# UnknownWatch_Top.net
KiCad netlist of a schematic drawn in EAGLE
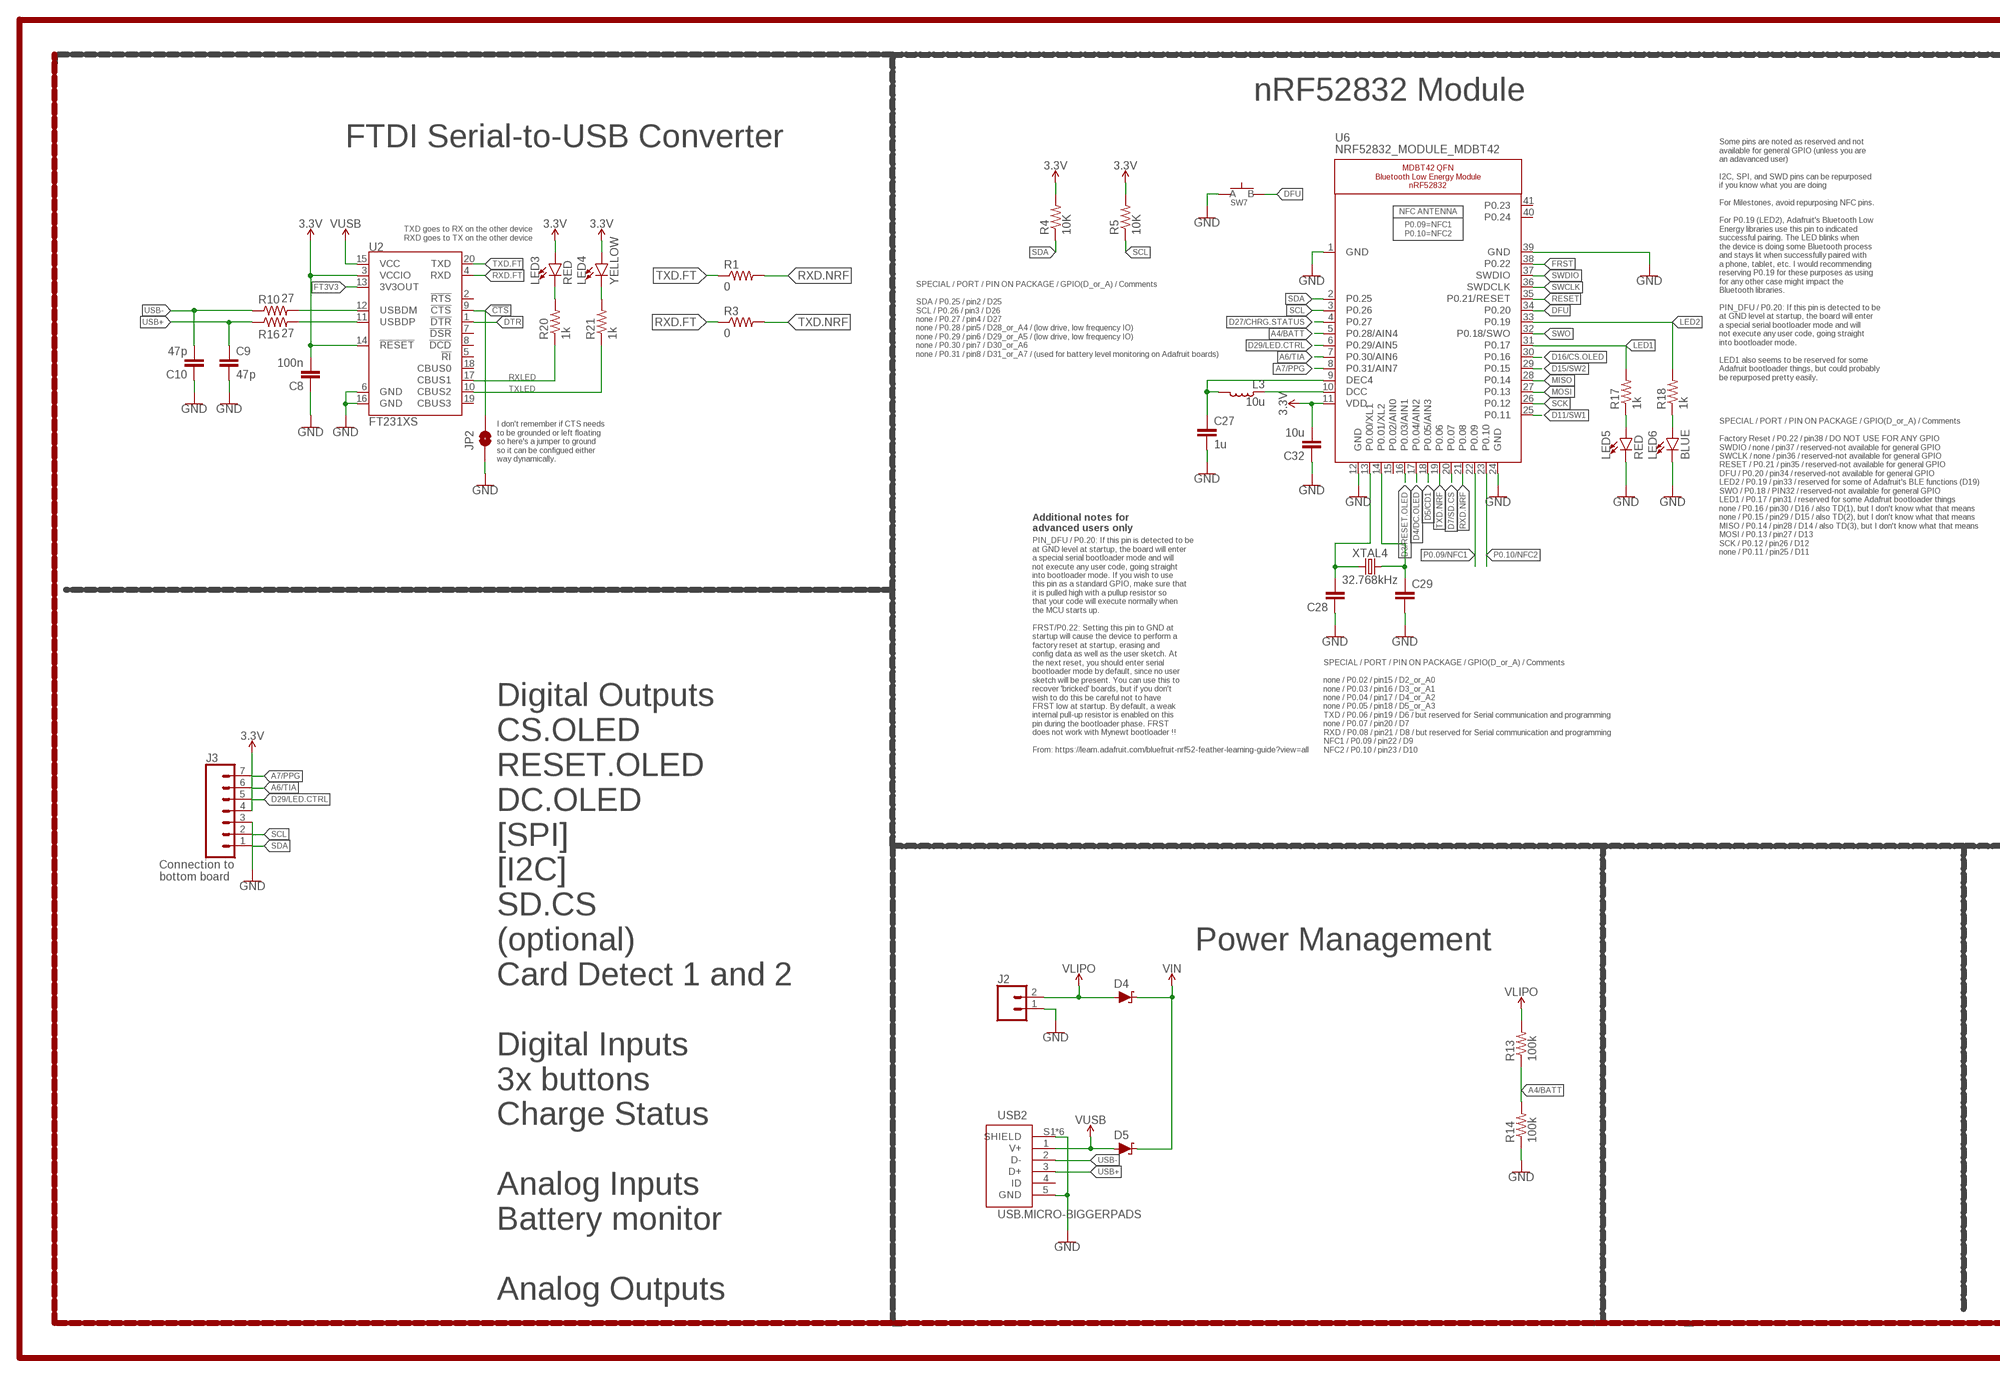
[diagram p0: schematic, sheet 1, part 1 of 2]
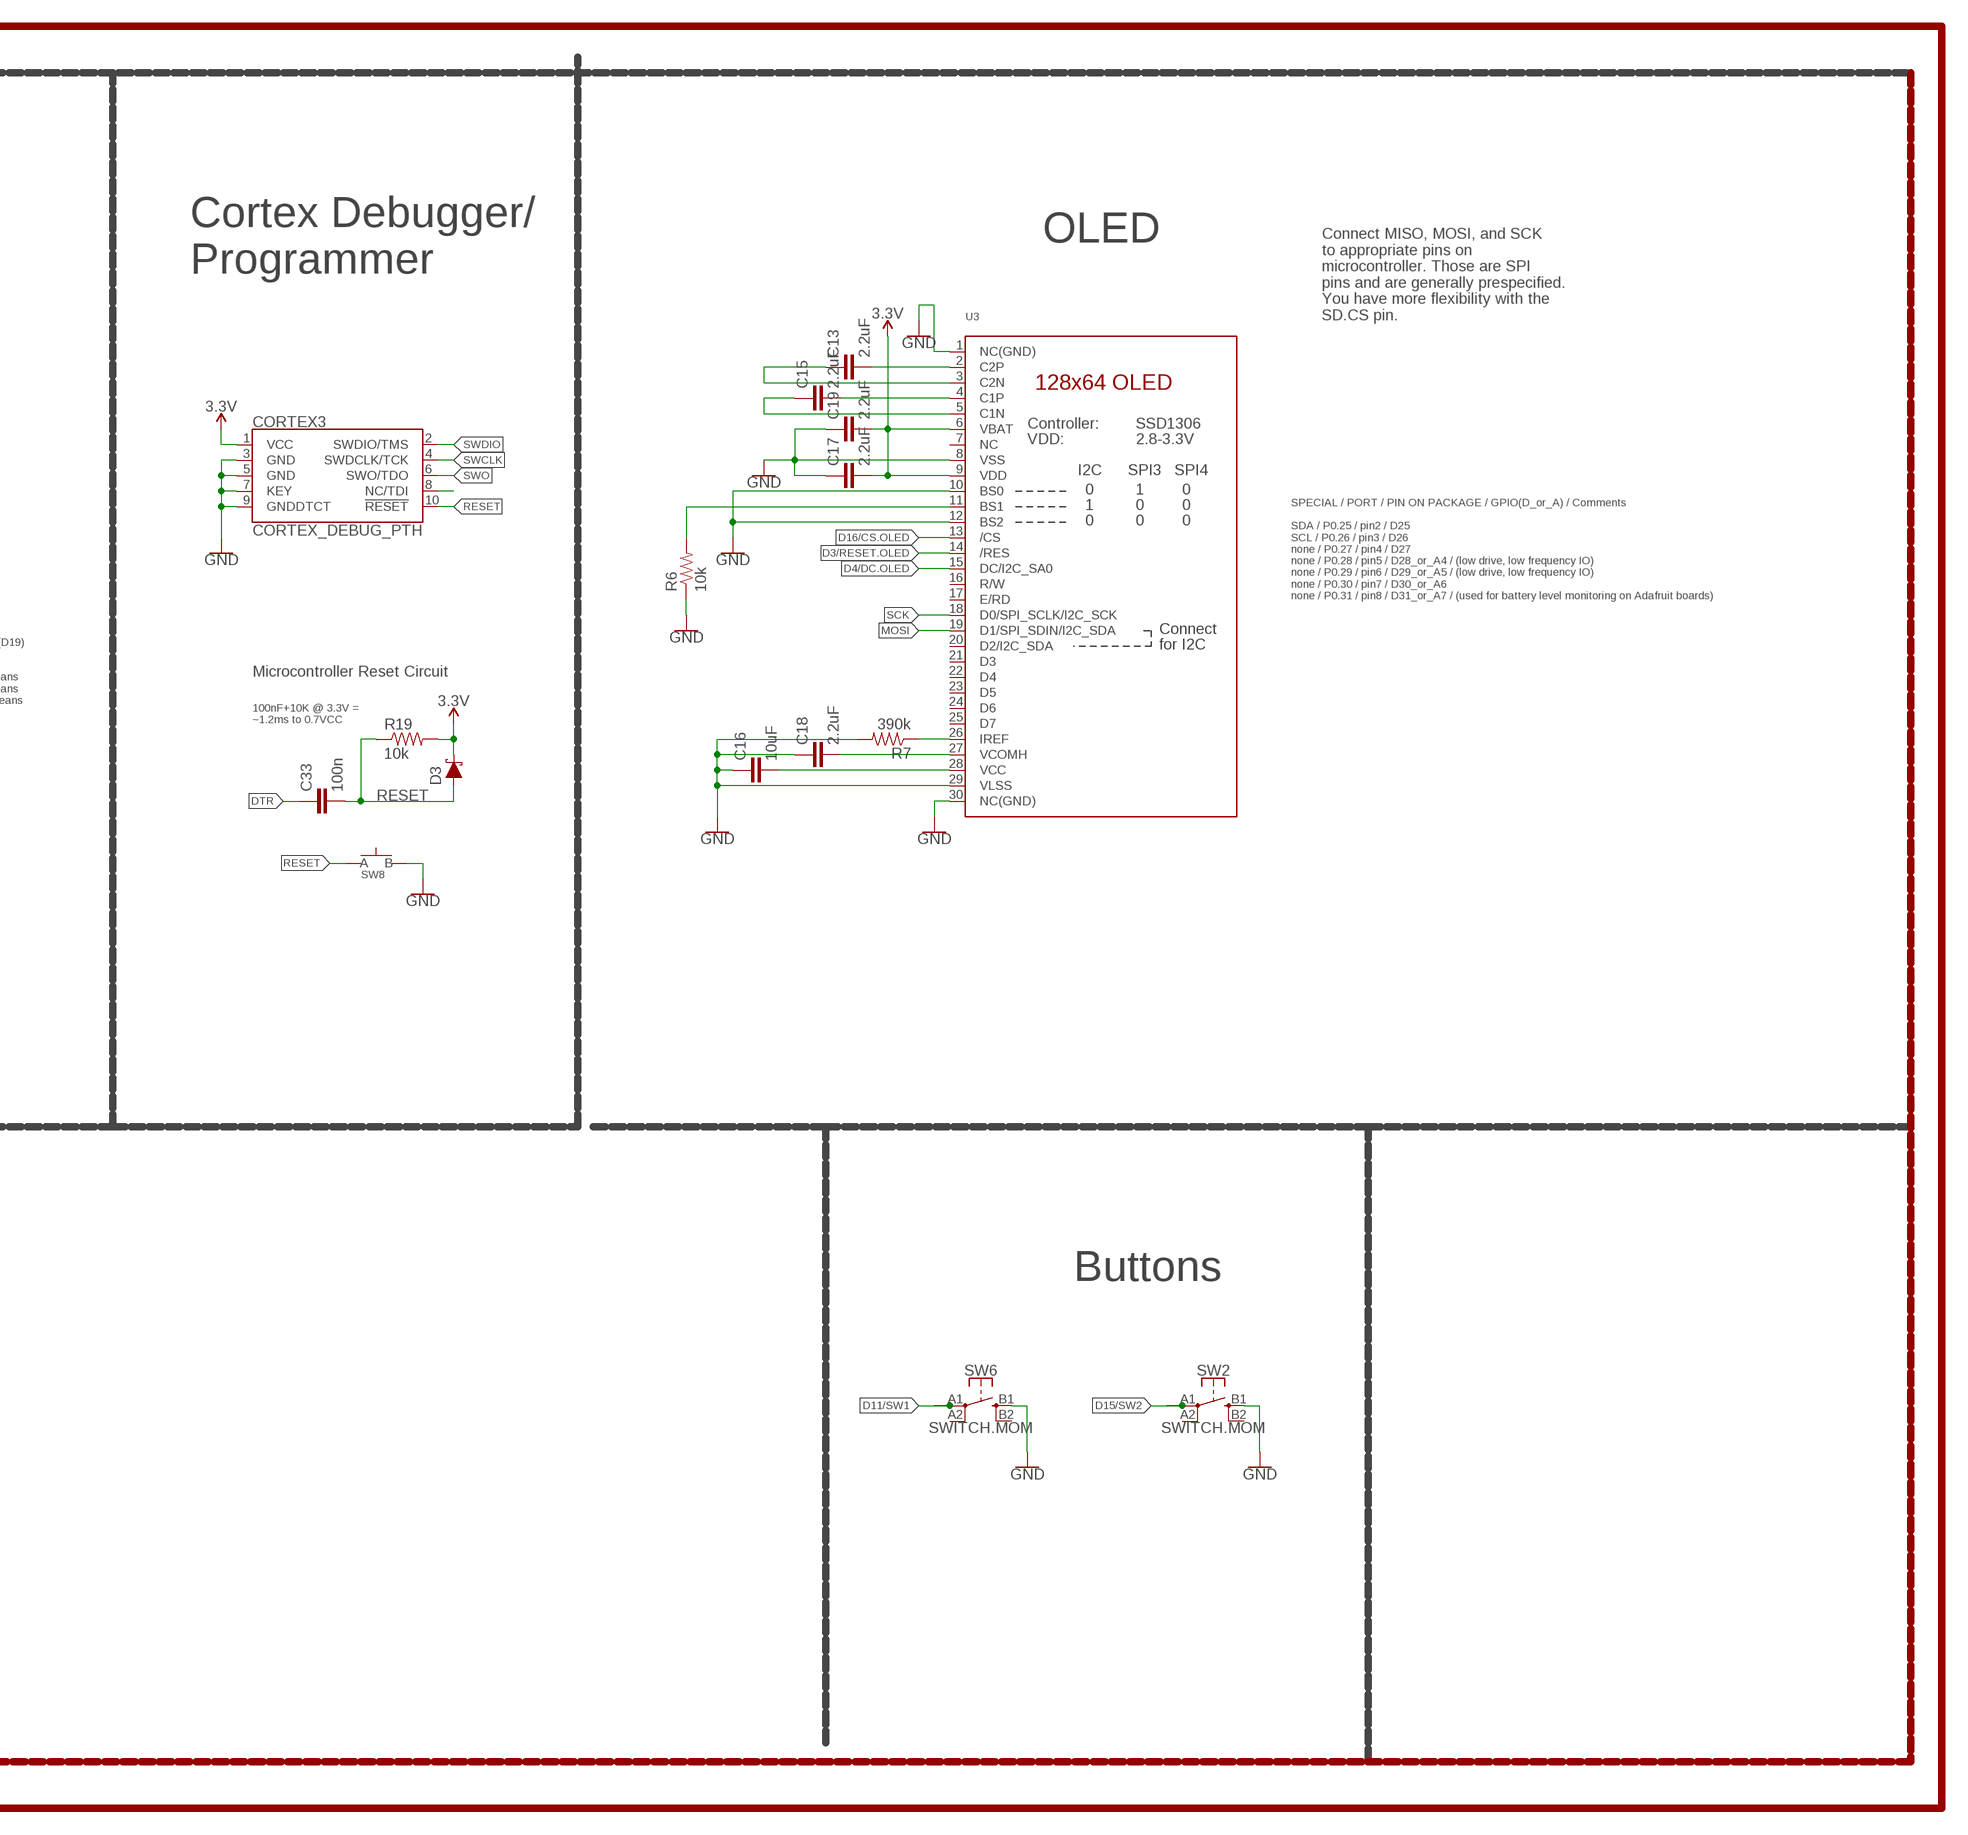
[diagram p1: schematic, sheet 1, part 2 of 2]

(export (version "E")
  (design (tool "Eeschema 10.0.6"))
  (components
    (comp (ref "C8")
      (value "100n")
      (footprint "eagle-import:C0603")
      (libsource (lib "eagle-import") (part "CAPACITOR0603"))
    )
    (comp (ref "C9")
      (value "47p")
      (footprint "eagle-import:C0603")
      (libsource (lib "eagle-import") (part "CAPACITOR0603"))
    )
    (comp (ref "C10")
      (value "47p")
      (footprint "eagle-import:C0603")
      (libsource (lib "eagle-import") (part "CAPACITOR0603"))
    )
    (comp (ref "C13")
      (value "2.2uF")
      (footprint "eagle-import:C0402")
      (libsource (lib "eagle-import") (part "CAPACITOR0402"))
    )
    (comp (ref "C15")
      (value "2.2uF")
      (footprint "eagle-import:C0402")
      (libsource (lib "eagle-import") (part "CAPACITOR0402"))
    )
    (comp (ref "C16")
      (value "10uF")
      (footprint "eagle-import:C0603")
      (libsource (lib "eagle-import") (part "CAPACITOR0603"))
    )
    (comp (ref "C17")
      (value "2.2uF")
      (footprint "eagle-import:C0402")
      (libsource (lib "eagle-import") (part "CAPACITOR0402"))
    )
    (comp (ref "C18")
      (value "2.2uF")
      (footprint "eagle-import:C0402")
      (libsource (lib "eagle-import") (part "CAPACITOR0402"))
    )
    (comp (ref "C19")
      (value "2.2uF")
      (footprint "eagle-import:C0402")
      (libsource (lib "eagle-import") (part "CAPACITOR0402"))
    )
    (comp (ref "C27")
      (value "1u")
      (footprint "eagle-import:C0603")
      (libsource (lib "eagle-import") (part "CAPACITOR0603"))
    )
    (comp (ref "C28")
      (value "CAPACITOR0603")
      (footprint "eagle-import:C0603")
      (libsource (lib "eagle-import") (part "CAPACITOR0603"))
    )
    (comp (ref "C29")
      (value "CAPACITOR0603")
      (footprint "eagle-import:C0603")
      (libsource (lib "eagle-import") (part "CAPACITOR0603"))
    )
    (comp (ref "C32")
      (value "10u")
      (footprint "eagle-import:C0805")
      (libsource (lib "eagle-import") (part "CAPACITOR0805"))
    )
    (comp (ref "C33")
      (value "100n")
      (footprint "eagle-import:C0603")
      (libsource (lib "eagle-import") (part "CAPACITOR0603"))
    )
    (comp (ref "CORTEX3")
      (value "CORTEX_DEBUG_PTH")
      (footprint "eagle-import:2X5-PTH-1.27MM")
      (libsource (lib "eagle-import") (part "CORTEX_DEBUG_PTH"))
    )
    (comp (ref "D3")
      (value "SCHOTTKY-USC")
      (footprint "eagle-import:USC")
      (libsource (lib "eagle-import") (part "SCHOTTKY-USC"))
    )
    (comp (ref "D4")
      (value "SCHOTTKY-USC")
      (footprint "eagle-import:USC")
      (libsource (lib "eagle-import") (part "SCHOTTKY-USC"))
    )
    (comp (ref "D5")
      (value "SCHOTTKY-USC")
      (footprint "eagle-import:USC")
      (libsource (lib "eagle-import") (part "SCHOTTKY-USC"))
    )
    (comp (ref "J2")
      (value "CONN_02")
      (footprint "eagle-import:1X02")
      (libsource (lib "eagle-import") (part "CONN_02"))
    )
    (comp (ref "J3")
      (value "CONN_07-1.27MM")
      (footprint "eagle-import:1X07_1.27MM")
      (libsource (lib "eagle-import") (part "CONN_07-1.27MM"))
    )
    (comp (ref "JP2")
      (value "JUMPER-SMT_2_NO_SILK")
      (footprint "eagle-import:SMT-JUMPER_2_NO_SILK")
      (libsource (lib "eagle-import") (part "JUMPER-SMT_2_NO_SILK"))
    )
    (comp (ref "L3")
      (value "10u")
      (footprint "eagle-import:L0603")
      (libsource (lib "eagle-import") (part "INDUCTOR0603"))
    )
    (comp (ref "LED3")
      (value "RED")
      (footprint "eagle-import:LED-0603")
      (libsource (lib "eagle-import") (part "LED0603"))
    )
    (comp (ref "LED4")
      (value "YELLOW")
      (footprint "eagle-import:LED-0603")
      (libsource (lib "eagle-import") (part "LED0603"))
    )
    (comp (ref "LED5")
      (value "RED")
      (footprint "eagle-import:LED-0603")
      (libsource (lib "eagle-import") (part "LED0603"))
    )
    (comp (ref "LED6")
      (value "BLUE")
      (footprint "eagle-import:LED-0603")
      (libsource (lib "eagle-import") (part "LED0603"))
    )
    (comp (ref "R1")
      (value "0")
      (footprint "eagle-import:R0603")
      (libsource (lib "eagle-import") (part "RESISTOR0603"))
    )
    (comp (ref "R3")
      (value "0")
      (footprint "eagle-import:R0603")
      (libsource (lib "eagle-import") (part "RESISTOR0603"))
    )
    (comp (ref "R4")
      (value "10K")
      (footprint "eagle-import:R0603")
      (libsource (lib "eagle-import") (part "RESISTOR0603"))
    )
    (comp (ref "R5")
      (value "10K")
      (footprint "eagle-import:R0603")
      (libsource (lib "eagle-import") (part "RESISTOR0603"))
    )
    (comp (ref "R6")
      (value "10k")
      (footprint "eagle-import:R0603")
      (libsource (lib "eagle-import") (part "RESISTOR0603"))
    )
    (comp (ref "R7")
      (value "390k")
      (footprint "eagle-import:R0603")
      (libsource (lib "eagle-import") (part "RESISTOR0603"))
    )
    (comp (ref "R10")
      (value "27")
      (footprint "eagle-import:R0603")
      (libsource (lib "eagle-import") (part "RESISTOR0603"))
    )
    (comp (ref "R13")
      (value "100k")
      (footprint "eagle-import:R0603")
      (libsource (lib "eagle-import") (part "RESISTOR0603"))
    )
    (comp (ref "R14")
      (value "100k")
      (footprint "eagle-import:R0603")
      (libsource (lib "eagle-import") (part "RESISTOR0603"))
    )
    (comp (ref "R16")
      (value "27")
      (footprint "eagle-import:R0603")
      (libsource (lib "eagle-import") (part "RESISTOR0603"))
    )
    (comp (ref "R17")
      (value "1k")
      (footprint "eagle-import:R0603")
      (libsource (lib "eagle-import") (part "RESISTOR0603"))
    )
    (comp (ref "R18")
      (value "1k")
      (footprint "eagle-import:R0603")
      (libsource (lib "eagle-import") (part "RESISTOR0603"))
    )
    (comp (ref "R19")
      (value "10k")
      (footprint "eagle-import:R0603")
      (libsource (lib "eagle-import") (part "RESISTOR0603"))
    )
    (comp (ref "R20")
      (value "1k")
      (footprint "eagle-import:R0603")
      (libsource (lib "eagle-import") (part "RESISTOR0603"))
    )
    (comp (ref "R21")
      (value "1k")
      (footprint "eagle-import:R0603")
      (libsource (lib "eagle-import") (part "RESISTOR0603"))
    )
    (comp (ref "SW2")
      (value "SWITCH.MOM")
      (footprint "eagle-import:TACTILE_SWITCH_SMD_6.2MM_TALL")
      (libsource (lib "eagle-import") (part "SWITCH.MOM"))
    )
    (comp (ref "SW6")
      (value "SWITCH.MOM")
      (footprint "eagle-import:TACTILE_SWITCH_SMD_6.2MM_TALL")
      (libsource (lib "eagle-import") (part "SWITCH.MOM"))
    )
    (comp (ref "SW7")
      (value "SPST-PTS830GG140-COPY.1-3")
      (footprint "eagle-import:BUTTON-GULLWING")
      (libsource (lib "eagle-import") (part "SPST-PTS830GG140-COPY.1-3"))
    )
    (comp (ref "SW8")
      (value "SPST-PTS830GG140-COPY.1-3")
      (footprint "eagle-import:BUTTON-GULLWING")
      (libsource (lib "eagle-import") (part "SPST-PTS830GG140-COPY.1-3"))
    )
    (comp (ref "U2")
      (value "FT231XS")
      (footprint "eagle-import:SSOP20_L")
      (libsource (lib "eagle-import") (part "FT231XS"))
    )
    (comp (ref "U3")
      (value "DISP_OLED_UG-2864HSWEG01-NO-WRAPAROUND")
      (footprint "eagle-import:UG-2864HSWEG01_0.96IN_NO-WRAPAROUND")
      (libsource (lib "eagle-import") (part "DISP_OLED_UG-2864HSWEG01-NO-WRAPAROUND"))
    )
    (comp (ref "U6")
      (value "NRF52832_MODULE_MDBT42")
      (footprint "eagle-import:BLE_MODULE_RAYTAC_MDBT42")
      (libsource (lib "eagle-import") (part "NRF52832_MODULE_MDBT42"))
    )
    (comp (ref "USB2")
      (value "USB.MICRO-BIGGERPADS")
      (footprint "eagle-import:USB-MICRO-01.BIGGERPADS")
      (libsource (lib "eagle-import") (part "USB.MICRO-BIGGERPADS"))
    )
    (comp (ref "XTAL4")
      (value "32.768kHz")
      (footprint "eagle-import:2-SMD.NOLEAD.2.0MMTO1.2MM")
      (libsource (lib "eagle-import") (part "CRYSTALECS-.327-12.5-12-C-TR"))
    )
  )
  (nets
    (net (code "1") (name "/RXLED") (class "Default")
      (node (ref "R20") (pin "1") (pinfunction "1_1") (pintype "passive"))
      (node (ref "U2") (pin "17") (pinfunction "CBUS1_17") (pintype "bidirectional"))
    )
    (net (code "2") (name "/TXLED") (class "Default")
      (node (ref "R21") (pin "1") (pinfunction "1_1") (pintype "passive"))
      (node (ref "U2") (pin "10") (pinfunction "CBUS2_10") (pintype "bidirectional"))
    )
    (net (code "3") (name "/~{CTS}") (class "Default")
      (node (ref "JP2") (pin "2") (pinfunction "2_2") (pintype "passive"))
      (node (ref "U2") (pin "9") (pinfunction "~{CTS}_9") (pintype "bidirectional"))
    )
    (net (code "4") (name "3.3V") (class "Default")
      (node (ref "C17") (pin "2") (pinfunction "2_2") (pintype "passive"))
      (node (ref "C19") (pin "2") (pinfunction "2_2") (pintype "passive"))
      (node (ref "C32") (pin "2") (pinfunction "2_2") (pintype "passive"))
      (node (ref "C8") (pin "2") (pinfunction "2_2") (pintype "passive"))
      (node (ref "CORTEX3") (pin "1") (pinfunction "VCC_1") (pintype "bidirectional"))
      (node (ref "D3") (pin "-") (pinfunction "C_-") (pintype "passive"))
      (node (ref "J3") (pin "4") (pinfunction "4_4") (pintype "passive"))
      (node (ref "LED3") (pin "A") (pinfunction "A_A") (pintype "passive"))
      (node (ref "LED4") (pin "A") (pinfunction "A_A") (pintype "passive"))
      (node (ref "R19") (pin "2") (pinfunction "2_2") (pintype "passive"))
      (node (ref "R4") (pin "2") (pinfunction "2_2") (pintype "passive"))
      (node (ref "R5") (pin "2") (pinfunction "2_2") (pintype "passive"))
      (node (ref "U2") (pin "14") (pinfunction "~{RESET}_14") (pintype "bidirectional"))
      (node (ref "U2") (pin "3") (pinfunction "VCCIO_3") (pintype "bidirectional"))
      (node (ref "U3") (pin "6") (pinfunction "VBAT_6") (pintype "input"))
      (node (ref "U3") (pin "9") (pinfunction "VDD_9") (pintype "power_in"))
      (node (ref "U6") (pin "11") (pinfunction "VDD_11") (pintype "bidirectional"))
    )
    (net (code "5") (name "A4{slash}BATT") (class "Default")
      (node (ref "R13") (pin "1") (pinfunction "1_1") (pintype "passive"))
      (node (ref "R14") (pin "2") (pinfunction "2_2") (pintype "passive"))
      (node (ref "U6") (pin "5") (pinfunction "P0.28/AIN4_5") (pintype "bidirectional"))
    )
    (net (code "6") (name "A6{slash}TIA") (class "Default")
      (node (ref "J3") (pin "6") (pinfunction "6_6") (pintype "passive"))
      (node (ref "U6") (pin "7") (pinfunction "P0.30/AIN6_7") (pintype "bidirectional"))
    )
    (net (code "7") (name "A7{slash}PPG") (class "Default")
      (node (ref "J3") (pin "7") (pinfunction "7_7") (pintype "passive"))
      (node (ref "U6") (pin "8") (pinfunction "P0.31/AIN7_8") (pintype "bidirectional"))
    )
    (net (code "8") (name "D3{slash}RESET.OLED") (class "Default")
      (node (ref "U3") (pin "14") (pinfunction "/RES_14") (pintype "input"))
      (node (ref "U6") (pin "16") (pinfunction "P0.03/AIN1_16") (pintype "bidirectional"))
    )
    (net (code "9") (name "D4{slash}DC.OLED") (class "Default")
      (node (ref "U3") (pin "15") (pinfunction "DC/I2C_SA0_15") (pintype "input"))
      (node (ref "U6") (pin "17") (pinfunction "P0.04/AIN2_17") (pintype "bidirectional"))
    )
    (net (code "10") (name "D5{slash}CD1") (class "Default")
      (node (ref "U6") (pin "18") (pinfunction "P0.05/AIN3_18") (pintype "bidirectional"))
    )
    (net (code "11") (name "D7{slash}SD.CS") (class "Default")
      (node (ref "U6") (pin "20") (pinfunction "P0.07_20") (pintype "bidirectional"))
    )
    (net (code "12") (name "D11{slash}SW1") (class "Default")
      (node (ref "SW6") (pin "A1") (pinfunction "1_A1") (pintype "passive"))
      (node (ref "U6") (pin "25") (pinfunction "P0.11_25") (pintype "bidirectional"))
    )
    (net (code "13") (name "D15{slash}SW2") (class "Default")
      (node (ref "SW2") (pin "A1") (pinfunction "1_A1") (pintype "passive"))
      (node (ref "U6") (pin "29") (pinfunction "P0.15_29") (pintype "bidirectional"))
    )
    (net (code "14") (name "D16{slash}CS.OLED") (class "Default")
      (node (ref "U3") (pin "13") (pinfunction "/CS_13") (pintype "input"))
      (node (ref "U6") (pin "30") (pinfunction "P0.16_30") (pintype "bidirectional"))
    )
    (net (code "15") (name "D27{slash}CHRG.STATUS") (class "Default")
      (node (ref "U6") (pin "4") (pinfunction "P0.27_4") (pintype "bidirectional"))
    )
    (net (code "16") (name "D29{slash}LED.CTRL") (class "Default")
      (node (ref "J3") (pin "5") (pinfunction "5_5") (pintype "passive"))
      (node (ref "U6") (pin "6") (pinfunction "P0.29/AIN5_6") (pintype "bidirectional"))
    )
    (net (code "17") (name "DFU") (class "Default")
      (node (ref "SW7") (pin "3") (pinfunction "B_3") (pintype "bidirectional"))
      (node (ref "U6") (pin "34") (pinfunction "P0.20_34") (pintype "bidirectional"))
    )
    (net (code "18") (name "DTR") (class "Default")
      (node (ref "C33") (pin "1") (pinfunction "1_1") (pintype "passive"))
      (node (ref "U2") (pin "1") (pinfunction "~{DTR}_1") (pintype "bidirectional"))
    )
    (net (code "19") (name "FRST") (class "Default")
      (node (ref "U6") (pin "38") (pinfunction "P0.22_38") (pintype "bidirectional"))
    )
    (net (code "20") (name "FT3V3") (class "Default")
      (node (ref "U2") (pin "13") (pinfunction "3V3OUT_13") (pintype "bidirectional"))
    )
    (net (code "21") (name "GND") (class "Default")
      (node (ref "C10") (pin "1") (pinfunction "1_1") (pintype "passive"))
      (node (ref "C16") (pin "1") (pinfunction "1_1") (pintype "passive"))
      (node (ref "C17") (pin "1") (pinfunction "1_1") (pintype "passive"))
      (node (ref "C18") (pin "1") (pinfunction "1_1") (pintype "passive"))
      (node (ref "C19") (pin "1") (pinfunction "1_1") (pintype "passive"))
      (node (ref "C27") (pin "2") (pinfunction "2_2") (pintype "passive"))
      (node (ref "C28") (pin "1") (pinfunction "1_1") (pintype "passive"))
      (node (ref "C29") (pin "2") (pinfunction "2_2") (pintype "passive"))
      (node (ref "C32") (pin "1") (pinfunction "1_1") (pintype "passive"))
      (node (ref "C8") (pin "1") (pinfunction "1_1") (pintype "passive"))
      (node (ref "C9") (pin "2") (pinfunction "2_2") (pintype "passive"))
      (node (ref "CORTEX3") (pin "3") (pinfunction "GND_3") (pintype "bidirectional"))
      (node (ref "CORTEX3") (pin "5") (pinfunction "GND_5") (pintype "bidirectional"))
      (node (ref "CORTEX3") (pin "7") (pinfunction "KEY_7") (pintype "bidirectional"))
      (node (ref "CORTEX3") (pin "9") (pinfunction "GNDDTCT_9") (pintype "bidirectional"))
      (node (ref "J2") (pin "1") (pinfunction "1_1") (pintype "passive"))
      (node (ref "J3") (pin "3") (pinfunction "3_3") (pintype "passive"))
      (node (ref "JP2") (pin "1") (pinfunction "1_1") (pintype "passive"))
      (node (ref "LED5") (pin "C") (pinfunction "C_C") (pintype "passive"))
      (node (ref "LED6") (pin "C") (pinfunction "C_C") (pintype "passive"))
      (node (ref "R14") (pin "1") (pinfunction "1_1") (pintype "passive"))
      (node (ref "R6") (pin "1") (pinfunction "1_1") (pintype "passive"))
      (node (ref "R7") (pin "2") (pinfunction "2_2") (pintype "passive"))
      (node (ref "SW2") (pin "B1") (pinfunction "3_B1") (pintype "passive"))
      (node (ref "SW6") (pin "B1") (pinfunction "3_B1") (pintype "passive"))
      (node (ref "SW7") (pin "1") (pinfunction "A_1") (pintype "bidirectional"))
      (node (ref "SW8") (pin "3") (pinfunction "B_3") (pintype "bidirectional"))
      (node (ref "U2") (pin "16") (pinfunction "GND_16") (pintype "bidirectional"))
      (node (ref "U2") (pin "6") (pinfunction "GND_6") (pintype "bidirectional"))
      (node (ref "U3") (pin "1") (pinfunction "NC(GND)_1") (pintype "input"))
      (node (ref "U3") (pin "10") (pinfunction "BS0_10") (pintype "input"))
      (node (ref "U3") (pin "12") (pinfunction "BS2_12") (pintype "input"))
      (node (ref "U3") (pin "29") (pinfunction "VLSS_29") (pintype "power_in"))
      (node (ref "U3") (pin "30") (pinfunction "NC(GND)_30") (pintype "input"))
      (node (ref "U3") (pin "8") (pinfunction "VSS_8") (pintype "power_in"))
      (node (ref "U6") (pin "1") (pinfunction "GND_1") (pintype "bidirectional"))
      (node (ref "U6") (pin "12") (pinfunction "GND_12") (pintype "bidirectional"))
      (node (ref "U6") (pin "24") (pinfunction "GND_24") (pintype "bidirectional"))
      (node (ref "U6") (pin "39") (pinfunction "GND_39") (pintype "bidirectional"))
      (node (ref "USB2") (pin "5") (pinfunction "GND_5") (pintype "bidirectional"))
      (node (ref "USB2") (pin "S1") (pinfunction "SHIELD_S1") (pintype "bidirectional"))
      (node (ref "USB2") (pin "S2") (pinfunction "SHIELD_S2") (pintype "bidirectional"))
      (node (ref "USB2") (pin "S3") (pinfunction "SHIELD_S3") (pintype "bidirectional"))
      (node (ref "USB2") (pin "S4") (pinfunction "SHIELD_S4") (pintype "bidirectional"))
      (node (ref "USB2") (pin "S5") (pinfunction "SHIELD_S5") (pintype "bidirectional"))
      (node (ref "USB2") (pin "S6") (pinfunction "SHIELD_S6") (pintype "bidirectional"))
    )
    (net (code "22") (name "LED1") (class "Default")
      (node (ref "R17") (pin "2") (pinfunction "2_2") (pintype "passive"))
      (node (ref "U6") (pin "31") (pinfunction "P0.17_31") (pintype "bidirectional"))
    )
    (net (code "23") (name "LED2") (class "Default")
      (node (ref "R18") (pin "2") (pinfunction "2_2") (pintype "passive"))
      (node (ref "U6") (pin "33") (pinfunction "P0.19_33") (pintype "bidirectional"))
    )
    (net (code "24") (name "MISO") (class "Default")
      (node (ref "U6") (pin "28") (pinfunction "P0.14_28") (pintype "bidirectional"))
    )
    (net (code "25") (name "MOSI") (class "Default")
      (node (ref "U3") (pin "19") (pinfunction "D1/SPI_SDIN/I2C_SDA_19") (pintype "bidirectional"))
      (node (ref "U6") (pin "27") (pinfunction "P0.13_27") (pintype "bidirectional"))
    )
    (net (code "26") (name "Net-(LED3-PadC)") (class "Default")
      (node (ref "LED3") (pin "C") (pinfunction "C_C") (pintype "passive"))
      (node (ref "R20") (pin "2") (pinfunction "2_2") (pintype "passive"))
    )
    (net (code "27") (name "Net-(LED4-PadC)") (class "Default")
      (node (ref "LED4") (pin "C") (pinfunction "C_C") (pintype "passive"))
      (node (ref "R21") (pin "2") (pinfunction "2_2") (pintype "passive"))
    )
    (net (code "28") (name "Net-(LED5-PadA)") (class "Default")
      (node (ref "LED5") (pin "A") (pinfunction "A_A") (pintype "passive"))
      (node (ref "R17") (pin "1") (pinfunction "1_1") (pintype "passive"))
    )
    (net (code "29") (name "Net-(LED6-PadA)") (class "Default")
      (node (ref "LED6") (pin "A") (pinfunction "A_A") (pintype "passive"))
      (node (ref "R18") (pin "1") (pinfunction "1_1") (pintype "passive"))
    )
    (net (code "30") (name "Net-(U2-USBDM)") (class "Default")
      (node (ref "R10") (pin "2") (pinfunction "2_2") (pintype "passive"))
      (node (ref "U2") (pin "12") (pinfunction "USBDM_12") (pintype "bidirectional"))
    )
    (net (code "31") (name "Net-(U2-USBDP)") (class "Default")
      (node (ref "R16") (pin "2") (pinfunction "2_2") (pintype "passive"))
      (node (ref "U2") (pin "11") (pinfunction "USBDP_11") (pintype "bidirectional"))
    )
    (net (code "32") (name "Net-(U3-BS1)") (class "Default")
      (node (ref "R6") (pin "2") (pinfunction "2_2") (pintype "passive"))
      (node (ref "U3") (pin "11") (pinfunction "BS1_11") (pintype "input"))
    )
    (net (code "33") (name "Net-(U3-C1N)") (class "Default")
      (node (ref "C15") (pin "1") (pinfunction "1_1") (pintype "passive"))
      (node (ref "U3") (pin "5") (pinfunction "C1N_5") (pintype "input"))
    )
    (net (code "34") (name "Net-(U3-C1P)") (class "Default")
      (node (ref "C15") (pin "2") (pinfunction "2_2") (pintype "passive"))
      (node (ref "U3") (pin "4") (pinfunction "C1P_4") (pintype "input"))
    )
    (net (code "35") (name "Net-(U3-C2N)") (class "Default")
      (node (ref "C13") (pin "1") (pinfunction "1_1") (pintype "passive"))
      (node (ref "U3") (pin "3") (pinfunction "C2N_3") (pintype "input"))
    )
    (net (code "36") (name "Net-(U3-C2P)") (class "Default")
      (node (ref "C13") (pin "2") (pinfunction "2_2") (pintype "passive"))
      (node (ref "U3") (pin "2") (pinfunction "C2P_2") (pintype "input"))
    )
    (net (code "37") (name "Net-(U3-IREF)") (class "Default")
      (node (ref "R7") (pin "1") (pinfunction "1_1") (pintype "passive"))
      (node (ref "U3") (pin "26") (pinfunction "IREF_26") (pintype "input"))
    )
    (net (code "38") (name "Net-(U3-VCC)") (class "Default")
      (node (ref "C16") (pin "2") (pinfunction "2_2") (pintype "passive"))
      (node (ref "U3") (pin "28") (pinfunction "VCC_28") (pintype "power_in"))
    )
    (net (code "39") (name "Net-(U3-VCOMH)") (class "Default")
      (node (ref "C18") (pin "2") (pinfunction "2_2") (pintype "passive"))
      (node (ref "U3") (pin "27") (pinfunction "VCOMH_27") (pintype "output"))
    )
    (net (code "40") (name "Net-(U6-DCC)") (class "Default")
      (node (ref "L3") (pin "1") (pinfunction "1_1") (pintype "passive"))
      (node (ref "U6") (pin "10") (pinfunction "DCC_10") (pintype "bidirectional"))
    )
    (net (code "41") (name "Net-(U6-DEC4)") (class "Default")
      (node (ref "C27") (pin "1") (pinfunction "1_1") (pintype "passive"))
      (node (ref "L3") (pin "2") (pinfunction "2_2") (pintype "passive"))
      (node (ref "U6") (pin "9") (pinfunction "DEC4_9") (pintype "bidirectional"))
    )
    (net (code "42") (name "Net-(U6-P0.00{slash}XL1)") (class "Default")
      (node (ref "C28") (pin "2") (pinfunction "2_2") (pintype "passive"))
      (node (ref "U6") (pin "13") (pinfunction "P0.00/XL1_13") (pintype "bidirectional"))
      (node (ref "XTAL4") (pin "P$1") (pinfunction "1_P$1") (pintype "passive"))
    )
    (net (code "43") (name "Net-(U6-P0.01{slash}XL2)") (class "Default")
      (node (ref "C29") (pin "1") (pinfunction "1_1") (pintype "passive"))
      (node (ref "U6") (pin "14") (pinfunction "P0.01/XL2_14") (pintype "bidirectional"))
      (node (ref "XTAL4") (pin "P$2") (pinfunction "2_P$2") (pintype "passive"))
    )
    (net (code "44") (name "P0.09{slash}NFC1") (class "Default")
      (node (ref "U6") (pin "22") (pinfunction "P0.09_22") (pintype "bidirectional"))
    )
    (net (code "45") (name "P0.10{slash}NFC2") (class "Default")
      (node (ref "U6") (pin "23") (pinfunction "P0.10_23") (pintype "bidirectional"))
    )
    (net (code "46") (name "RESET") (class "Default")
      (node (ref "C33") (pin "2") (pinfunction "2_2") (pintype "passive"))
      (node (ref "CORTEX3") (pin "10") (pinfunction "~{RESET}_10") (pintype "bidirectional"))
      (node (ref "D3") (pin "+") (pinfunction "A_+") (pintype "passive"))
      (node (ref "R19") (pin "1") (pinfunction "1_1") (pintype "passive"))
      (node (ref "SW8") (pin "1") (pinfunction "A_1") (pintype "bidirectional"))
      (node (ref "U6") (pin "35") (pinfunction "P0.21/RESET_35") (pintype "bidirectional"))
    )
    (net (code "47") (name "RXD.FT") (class "Default")
      (node (ref "R3") (pin "1") (pinfunction "1_1") (pintype "passive"))
      (node (ref "U2") (pin "4") (pinfunction "RXD_4") (pintype "bidirectional"))
    )
    (net (code "48") (name "RXD.NRF") (class "Default")
      (node (ref "R1") (pin "2") (pinfunction "2_2") (pintype "passive"))
      (node (ref "U6") (pin "21") (pinfunction "P0.08_21") (pintype "bidirectional"))
    )
    (net (code "49") (name "SCK") (class "Default")
      (node (ref "U3") (pin "18") (pinfunction "D0/SPI_SCLK/I2C_SCK_18") (pintype "bidirectional"))
      (node (ref "U6") (pin "26") (pinfunction "P0.12_26") (pintype "bidirectional"))
    )
    (net (code "50") (name "SCL") (class "Default")
      (node (ref "J3") (pin "2") (pinfunction "2_2") (pintype "passive"))
      (node (ref "R5") (pin "1") (pinfunction "1_1") (pintype "passive"))
      (node (ref "U6") (pin "3") (pinfunction "P0.26_3") (pintype "bidirectional"))
    )
    (net (code "51") (name "SDA") (class "Default")
      (node (ref "J3") (pin "1") (pinfunction "1_1") (pintype "passive"))
      (node (ref "R4") (pin "1") (pinfunction "1_1") (pintype "passive"))
      (node (ref "U6") (pin "2") (pinfunction "P0.25_2") (pintype "bidirectional"))
    )
    (net (code "52") (name "SWCLK") (class "Default")
      (node (ref "CORTEX3") (pin "4") (pinfunction "SWDCLK/TCK_4") (pintype "bidirectional"))
      (node (ref "U6") (pin "36") (pinfunction "SWDCLK_36") (pintype "bidirectional"))
    )
    (net (code "53") (name "SWDIO") (class "Default")
      (node (ref "CORTEX3") (pin "2") (pinfunction "SWDIO/TMS_2") (pintype "bidirectional"))
      (node (ref "U6") (pin "37") (pinfunction "SWDIO_37") (pintype "bidirectional"))
    )
    (net (code "54") (name "SWO") (class "Default")
      (node (ref "CORTEX3") (pin "6") (pinfunction "SWO/TDO_6") (pintype "bidirectional"))
      (node (ref "U6") (pin "32") (pinfunction "P0.18/SWO_32") (pintype "bidirectional"))
    )
    (net (code "55") (name "TXD.FT") (class "Default")
      (node (ref "R1") (pin "1") (pinfunction "1_1") (pintype "passive"))
      (node (ref "U2") (pin "20") (pinfunction "TXD_20") (pintype "bidirectional"))
    )
    (net (code "56") (name "TXD.NRF") (class "Default")
      (node (ref "R3") (pin "2") (pinfunction "2_2") (pintype "passive"))
      (node (ref "U6") (pin "19") (pinfunction "P0.06_19") (pintype "bidirectional"))
    )
    (net (code "57") (name "USB+") (class "Default")
      (node (ref "C9") (pin "1") (pinfunction "1_1") (pintype "passive"))
      (node (ref "R16") (pin "1") (pinfunction "1_1") (pintype "passive"))
      (node (ref "USB2") (pin "3") (pinfunction "D+_3") (pintype "bidirectional"))
    )
    (net (code "58") (name "USB-") (class "Default")
      (node (ref "C10") (pin "2") (pinfunction "2_2") (pintype "passive"))
      (node (ref "R10") (pin "1") (pinfunction "1_1") (pintype "passive"))
      (node (ref "USB2") (pin "2") (pinfunction "D-_2") (pintype "bidirectional"))
    )
    (net (code "59") (name "VIN") (class "Default")
      (node (ref "D4") (pin "-") (pinfunction "C_-") (pintype "passive"))
      (node (ref "D5") (pin "-") (pinfunction "C_-") (pintype "passive"))
    )
    (net (code "60") (name "VLIPO") (class "Default")
      (node (ref "D4") (pin "+") (pinfunction "A_+") (pintype "passive"))
      (node (ref "J2") (pin "2") (pinfunction "2_2") (pintype "passive"))
      (node (ref "R13") (pin "2") (pinfunction "2_2") (pintype "passive"))
    )
    (net (code "61") (name "VUSB") (class "Default")
      (node (ref "D5") (pin "+") (pinfunction "A_+") (pintype "passive"))
      (node (ref "U2") (pin "15") (pinfunction "VCC_15") (pintype "bidirectional"))
      (node (ref "USB2") (pin "1") (pinfunction "V+_1") (pintype "bidirectional"))
    )
    (net (code "62") (name "unconnected-(CORTEX3-NC{slash}TDI-Pad8)") (class "Default")
      (node (ref "CORTEX3") (pin "8") (pinfunction "NC/TDI_8") (pintype "bidirectional"))
    )
    (net (code "63") (name "unconnected-(SW2-2-PadA2)") (class "Default")
      (node (ref "SW2") (pin "A2") (pinfunction "2_A2") (pintype "passive"))
    )
    (net (code "64") (name "unconnected-(SW2-4-PadB2)") (class "Default")
      (node (ref "SW2") (pin "B2") (pinfunction "4_B2") (pintype "passive"))
    )
    (net (code "65") (name "unconnected-(SW6-2-PadA2)") (class "Default")
      (node (ref "SW6") (pin "A2") (pinfunction "2_A2") (pintype "passive"))
    )
    (net (code "66") (name "unconnected-(SW6-4-PadB2)") (class "Default")
      (node (ref "SW6") (pin "B2") (pinfunction "4_B2") (pintype "passive"))
    )
    (net (code "67") (name "unconnected-(U2-CBUS0-Pad18)") (class "Default")
      (node (ref "U2") (pin "18") (pinfunction "CBUS0_18") (pintype "bidirectional"))
    )
    (net (code "68") (name "unconnected-(U2-CBUS3-Pad19)") (class "Default")
      (node (ref "U2") (pin "19") (pinfunction "CBUS3_19") (pintype "bidirectional"))
    )
    (net (code "69") (name "unconnected-(U2-~{DCD}-Pad8)") (class "Default")
      (node (ref "U2") (pin "8") (pinfunction "~{DCD}_8") (pintype "bidirectional"))
    )
    (net (code "70") (name "unconnected-(U2-~{DSR}-Pad7)") (class "Default")
      (node (ref "U2") (pin "7") (pinfunction "~{DSR}_7") (pintype "bidirectional"))
    )
    (net (code "71") (name "unconnected-(U2-~{RI}-Pad5)") (class "Default")
      (node (ref "U2") (pin "5") (pinfunction "~{RI}_5") (pintype "bidirectional"))
    )
    (net (code "72") (name "unconnected-(U2-~{RTS}-Pad2)") (class "Default")
      (node (ref "U2") (pin "2") (pinfunction "~{RTS}_2") (pintype "bidirectional"))
    )
    (net (code "73") (name "unconnected-(U3-D2{slash}I2C_SDA-Pad20)") (class "Default")
      (node (ref "U3") (pin "20") (pinfunction "D2/I2C_SDA_20") (pintype "bidirectional"))
    )
    (net (code "74") (name "unconnected-(U3-D3-Pad21)") (class "Default")
      (node (ref "U3") (pin "21") (pinfunction "D3_21") (pintype "bidirectional"))
    )
    (net (code "75") (name "unconnected-(U3-D4-Pad22)") (class "Default")
      (node (ref "U3") (pin "22") (pinfunction "D4_22") (pintype "bidirectional"))
    )
    (net (code "76") (name "unconnected-(U3-D5-Pad23)") (class "Default")
      (node (ref "U3") (pin "23") (pinfunction "D5_23") (pintype "bidirectional"))
    )
    (net (code "77") (name "unconnected-(U3-D6-Pad24)") (class "Default")
      (node (ref "U3") (pin "24") (pinfunction "D6_24") (pintype "bidirectional"))
    )
    (net (code "78") (name "unconnected-(U3-D7-Pad25)") (class "Default")
      (node (ref "U3") (pin "25") (pinfunction "D7_25") (pintype "bidirectional"))
    )
    (net (code "79") (name "unconnected-(U3-E{slash}RD-Pad17)") (class "Default")
      (node (ref "U3") (pin "17") (pinfunction "E/RD_17") (pintype "input"))
    )
    (net (code "80") (name "unconnected-(U3-NC-Pad7)") (class "Default")
      (node (ref "U3") (pin "7") (pinfunction "NC_7") (pintype "no_connect"))
    )
    (net (code "81") (name "unconnected-(U3-R{slash}W-Pad16)") (class "Default")
      (node (ref "U3") (pin "16") (pinfunction "R/W_16") (pintype "input"))
    )
    (net (code "82") (name "unconnected-(U6-P0.02{slash}AIN0-Pad15)") (class "Default")
      (node (ref "U6") (pin "15") (pinfunction "P0.02/AIN0_15") (pintype "bidirectional"))
    )
    (net (code "83") (name "unconnected-(U6-P0.23-Pad41)") (class "Default")
      (node (ref "U6") (pin "41") (pinfunction "P0.23_41") (pintype "bidirectional"))
    )
    (net (code "84") (name "unconnected-(U6-P0.24-Pad40)") (class "Default")
      (node (ref "U6") (pin "40") (pinfunction "P0.24_40") (pintype "bidirectional"))
    )
    (net (code "85") (name "unconnected-(USB2-ID-Pad4)") (class "Default")
      (node (ref "USB2") (pin "4") (pinfunction "ID_4") (pintype "bidirectional"))
    )
  )
)
